# LCD.net
KiCad netlist of a schematic drawn in Altium Designer
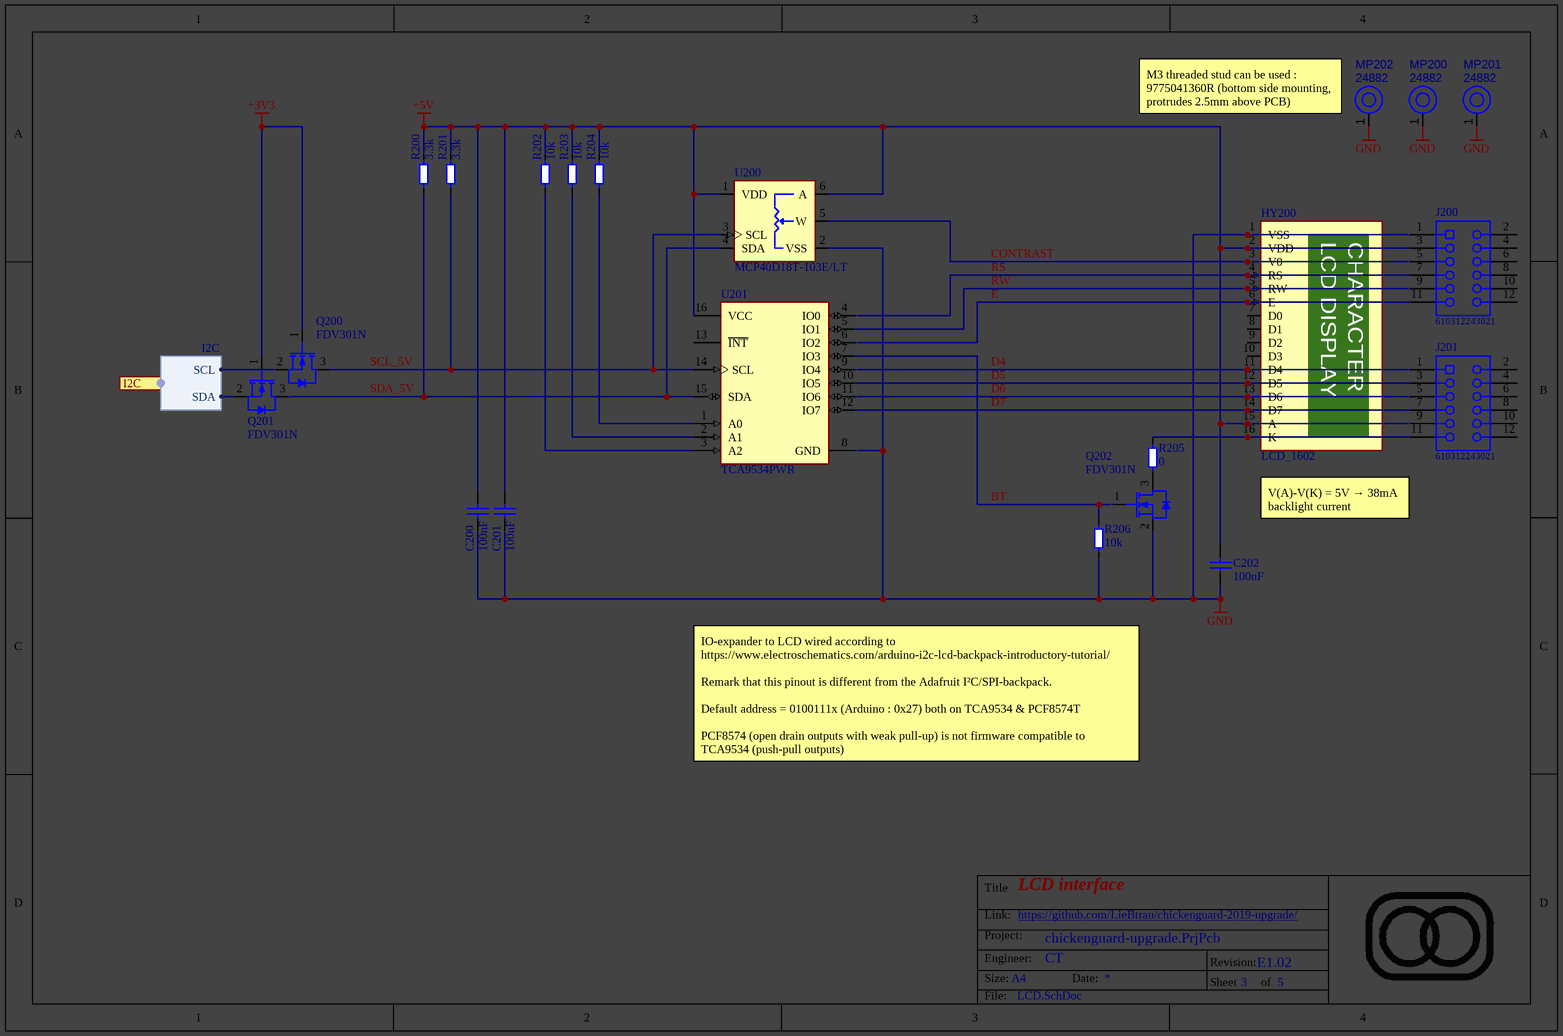
[diagram p0: LCD.SchDoc]

(export (version "E")
  (design (tool "Eeschema 10.0.6"))
  (components
    (comp (ref "C200")
      (value "100nF")
      (footprint "0603-C-L")
      (description "WCAP-CSGP Multilayer Ceramic Chip Capacitor, General Purpose, size 0603, X7R, 100nF, 25VDC")
      (fields (field (name "TOLERANCE") "10%") (field (name "Comment") "Capacitor 100nF +/-10% 25V X7R 0603"))
      (libsource (lib "7c7 Engineering") (part "CAP-NP-2"))
    )
    (comp (ref "C201")
      (value "100nF")
      (footprint "0603-C-L")
      (description "WCAP-CSGP Multilayer Ceramic Chip Capacitor, General Purpose, size 0603, X7R, 100nF, 25VDC")
      (fields (field (name "TOLERANCE") "10%") (field (name "Comment") "Capacitor 100nF +/-10% 25V X7R 0603"))
      (libsource (lib "7c7 Engineering") (part "CAP-NP-2"))
    )
    (comp (ref "C202")
      (value "100nF")
      (footprint "0603-C-L")
      (description "WCAP-CSGP Multilayer Ceramic Chip Capacitor, General Purpose, size 0603, X7R, 100nF, 25VDC")
      (fields (field (name "TOLERANCE") "10%") (field (name "Comment") "Capacitor 100nF +/-10% 25V X7R 0603"))
      (libsource (lib "7c7 Engineering") (part "CAP-NP-2"))
    )
    (comp (ref "HY200")
      (value "LCD_1602")
      (footprint "LCD_1602-BottomEntry")
      (description "2x16 character LCD display")
      (libsource (lib "7c7 Engineering") (part "CHAR_LCD_PARALLEL"))
    )
    (comp (ref "J200")
      (value "610312243021")
      (footprint "610312243021")
      (description "WR-PHD Socket Header, SMT, pitch 2.54mm, Dual Row, Vertical, 12p")
      (fields (field (name "MANUFACTURER") "Wurth Elektronik"))
      (libsource (lib "7c7 Engineering") (part "Symbol"))
    )
    (comp (ref "J201")
      (value "610312243021")
      (footprint "610312243021")
      (description "WR-PHD Socket Header, SMT, pitch 2.54mm, Dual Row, Vertical, 12p")
      (fields (field (name "MANUFACTURER") "Wurth Elektronik"))
      (libsource (lib "7c7 Engineering") (part "Symbol"))
    )
    (comp (ref "MP200")
      (value "24882")
      (footprint "24882-Footprint-1")
      (description "Steel SMT Standoff, M3 - 3mm L")
      (libsource (lib "7c7 Engineering") (part "MECH_BOM"))
    )
    (comp (ref "MP201")
      (value "24882")
      (footprint "24882-Footprint-1")
      (description "Steel SMT Standoff, M3 - 3mm L")
      (libsource (lib "7c7 Engineering") (part "MECH_BOM"))
    )
    (comp (ref "MP202")
      (value "24882")
      (footprint "24882-Footprint-1")
      (description "Steel SMT Standoff, M3 - 3mm L")
      (libsource (lib "7c7 Engineering") (part "MECH_BOM"))
    )
    (comp (ref "Q200")
      (value "FDV301N")
      (footprint "SOT-23-3-N")
      (description "Transistor MOSFET N-Ch. 25V 220mA 0, 35W 4Ohm SOT23")
      (fields (field (name "JLCPCB PART #") "C15310"))
      (libsource (lib "7c7 Engineering") (part "NEMOS-GSD-3"))
    )
    (comp (ref "Q201")
      (value "FDV301N")
      (footprint "SOT-23-3-N")
      (description "Transistor MOSFET N-Ch. 25V 220mA 0, 35W 4Ohm SOT23")
      (fields (field (name "JLCPCB PART #") "C15310"))
      (libsource (lib "7c7 Engineering") (part "NEMOS-GSD-3"))
    )
    (comp (ref "Q202")
      (value "FDV301N")
      (footprint "SOT-23-3-N")
      (description "Transistor MOSFET N-Ch. 25V 220mA 0, 35W 4Ohm SOT23")
      (fields (field (name "JLCPCB PART #") "C15310"))
      (libsource (lib "7c7 Engineering") (part "NEMOS-GSD-3"))
    )
    (comp (ref "R200")
      (value "3.3k")
      (footprint "0603-R-N")
      (description "Chip Resistor, Thick Film, General Purpose, 0603, 100mW, 50V, 3.3 kOhm, +/-1%")
      (fields (field (name "TOLERANCE") "1%") (field (name "JLCPCB PART #") "C22978"))
      (libsource (lib "7c7 Engineering") (part "RES"))
    )
    (comp (ref "R201")
      (value "3.3k")
      (footprint "0603-R-N")
      (description "Chip Resistor, Thick Film, General Purpose, 0603, 100mW, 50V, 3.3 kOhm, +/-1%")
      (fields (field (name "TOLERANCE") "1%") (field (name "JLCPCB PART #") "C22978"))
      (libsource (lib "7c7 Engineering") (part "RES"))
    )
    (comp (ref "R202")
      (value "10k")
      (footprint "0603-R-N")
      (description "Chip Resistor, Thick Film, General Purpose, 0603, 100mW, 50V, 10 kOhm, +/-1%")
      (fields (field (name "TOLERANCE") "1%") (field (name "JLCPCB PART #") "C25804"))
      (libsource (lib "7c7 Engineering") (part "RES"))
    )
    (comp (ref "R203")
      (value "10k")
      (footprint "0603-R-N")
      (description "Chip Resistor, Thick Film, General Purpose, 0603, 100mW, 50V, 10 kOhm, +/-1%")
      (fields (field (name "TOLERANCE") "1%") (field (name "JLCPCB PART #") "C25804"))
      (libsource (lib "7c7 Engineering") (part "RES"))
    )
    (comp (ref "R204")
      (value "10k")
      (footprint "0603-R-N")
      (description "Chip Resistor, Thick Film, General Purpose, 0603, 100mW, 50V, 10 kOhm, +/-1%")
      (fields (field (name "TOLERANCE") "1%") (field (name "JLCPCB PART #") "C25804"))
      (libsource (lib "7c7 Engineering") (part "RES"))
    )
    (comp (ref "R205")
      (value "0")
      (footprint "0603-R-N")
      (description "Chip Jumper, Thick Film, Jumper, 0603, 100mW, 1A, 0 Ohm, <50 mOhm")
      (fields (field (name "TOLERANCE") "50 mOhm") (field (name "JLCPCB PART #") "C21189"))
      (libsource (lib "7c7 Engineering") (part "RES"))
    )
    (comp (ref "R206")
      (value "10k")
      (footprint "0603-R-N")
      (description "Chip Resistor, Thick Film, General Purpose, 0603, 100mW, 50V, 10 kOhm, +/-1%")
      (fields (field (name "TOLERANCE") "1%") (field (name "JLCPCB PART #") "C25804"))
      (libsource (lib "7c7 Engineering") (part "RES"))
    )
    (comp (ref "U200")
      (value "MCP40D18T-103E/LT")
      (footprint "SOT363-N")
      (description "Digital Potentiometer 10kOhm 128POS Volatile Linear Automotive 6-Pin SC-70 T/R")
      (fields (field (name "TOLERANCE") "20%"))
      (libsource (lib "7c7 Engineering") (part "IN-DPOT-MCP4018-6"))
    )
    (comp (ref "U201")
      (value "TCA9534PWR")
      (footprint "TSSOP16-0.65-4.4-L")
      (description "8-bit I/O expander, I2C/SMBus, 400kHz, 1.65 to 5.5V, TSSOP-16")
      (libsource (lib "7c7 Engineering") (part "04628dd91dbb09866b58f3fb2ae999f"))
    )
  )
  (nets
    (net (code "2") (name "+3V3") (class "Default")
      (node (ref "Q200") (pin "1") (pinfunction "G_1") (pintype "passive"))
      (node (ref "Q201") (pin "1") (pinfunction "G_1") (pintype "passive"))
    )
    (net (code "3") (name "+5V") (class "Default")
      (node (ref "C200") (pin "2") (pinfunction "2_2") (pintype "passive"))
      (node (ref "C201") (pin "2") (pinfunction "2_2") (pintype "passive"))
      (node (ref "C202") (pin "2") (pinfunction "2_2") (pintype "passive"))
      (node (ref "HY200") (pin "15") (pinfunction "A_15") (pintype "power_in"))
      (node (ref "HY200") (pin "2") (pinfunction "VDD_2") (pintype "power_in"))
      (node (ref "J200") (pin "3") (pinfunction "3_3") (pintype "passive"))
      (node (ref "J201") (pin "9") (pinfunction "9_9") (pintype "passive"))
      (node (ref "R200") (pin "2") (pinfunction "2_2") (pintype "passive"))
      (node (ref "R201") (pin "2") (pinfunction "2_2") (pintype "passive"))
      (node (ref "R202") (pin "2") (pinfunction "2_2") (pintype "passive"))
      (node (ref "R203") (pin "2") (pinfunction "2_2") (pintype "passive"))
      (node (ref "R204") (pin "2") (pinfunction "2_2") (pintype "passive"))
      (node (ref "U200") (pin "1") (pinfunction "VDD_1") (pintype "power_in"))
      (node (ref "U200") (pin "6") (pinfunction "A_6") (pintype "passive"))
      (node (ref "U201") (pin "16") (pinfunction "VCC_16") (pintype "power_in"))
    )
    (net (code "4") (name "/BT") (class "Default")
      (node (ref "Q202") (pin "1") (pinfunction "G_1") (pintype "passive"))
      (node (ref "R206") (pin "2") (pinfunction "2_2") (pintype "passive"))
      (node (ref "U201") (pin "7") (pinfunction "IO3_7") (pintype "bidirectional"))
    )
    (net (code "5") (name "/CONTRAST") (class "Default")
      (node (ref "HY200") (pin "3") (pinfunction "V0_3") (pintype "power_in"))
      (node (ref "J200") (pin "5") (pinfunction "5_5") (pintype "passive"))
      (node (ref "U200") (pin "5") (pinfunction "W_5") (pintype "passive"))
    )
    (net (code "6") (name "/D4") (class "Default")
      (node (ref "HY200") (pin "11") (pinfunction "D4_11") (pintype "bidirectional"))
      (node (ref "J201") (pin "1") (pinfunction "1_1") (pintype "passive"))
      (node (ref "U201") (pin "9") (pinfunction "IO4_9") (pintype "bidirectional"))
    )
    (net (code "7") (name "/D5") (class "Default")
      (node (ref "HY200") (pin "12") (pinfunction "D5_12") (pintype "bidirectional"))
      (node (ref "J201") (pin "3") (pinfunction "3_3") (pintype "passive"))
      (node (ref "U201") (pin "10") (pinfunction "IO5_10") (pintype "bidirectional"))
    )
    (net (code "8") (name "/D6") (class "Default")
      (node (ref "HY200") (pin "13") (pinfunction "D6_13") (pintype "bidirectional"))
      (node (ref "J201") (pin "5") (pinfunction "5_5") (pintype "passive"))
      (node (ref "U201") (pin "11") (pinfunction "IO6_11") (pintype "bidirectional"))
    )
    (net (code "9") (name "/D7") (class "Default")
      (node (ref "HY200") (pin "14") (pinfunction "D7_14") (pintype "bidirectional"))
      (node (ref "J201") (pin "7") (pinfunction "7_7") (pintype "passive"))
      (node (ref "U201") (pin "12") (pinfunction "IO7_12") (pintype "bidirectional"))
    )
    (net (code "10") (name "/E") (class "Default")
      (node (ref "HY200") (pin "6") (pinfunction "E_6") (pintype "input"))
      (node (ref "J200") (pin "11") (pinfunction "11_11") (pintype "passive"))
      (node (ref "U201") (pin "6") (pinfunction "IO2_6") (pintype "bidirectional"))
    )
    (net (code "11") (name "/RS") (class "Default")
      (node (ref "HY200") (pin "4") (pinfunction "RS_4") (pintype "input"))
      (node (ref "J200") (pin "7") (pinfunction "7_7") (pintype "passive"))
      (node (ref "U201") (pin "4") (pinfunction "IO0_4") (pintype "bidirectional"))
    )
    (net (code "12") (name "/RW") (class "Default")
      (node (ref "HY200") (pin "5") (pinfunction "RW_5") (pintype "input"))
      (node (ref "J200") (pin "9") (pinfunction "9_9") (pintype "passive"))
      (node (ref "U201") (pin "5") (pinfunction "IO1_5") (pintype "bidirectional"))
    )
    (net (code "13") (name "/SCL") (class "Default")
      (node (ref "Q200") (pin "2") (pinfunction "S_2") (pintype "passive"))
    )
    (net (code "14") (name "/SCL_5V") (class "Default")
      (node (ref "Q200") (pin "3") (pinfunction "D_3") (pintype "passive"))
      (node (ref "R201") (pin "1") (pinfunction "1_1") (pintype "passive"))
      (node (ref "U200") (pin "3") (pinfunction "SCL_3") (pintype "input"))
      (node (ref "U201") (pin "14") (pinfunction "SCL_14") (pintype "input"))
    )
    (net (code "15") (name "/SDA") (class "Default")
      (node (ref "Q201") (pin "2") (pinfunction "S_2") (pintype "passive"))
    )
    (net (code "16") (name "/SDA_5V") (class "Default")
      (node (ref "Q201") (pin "3") (pinfunction "D_3") (pintype "passive"))
      (node (ref "R200") (pin "1") (pinfunction "1_1") (pintype "passive"))
      (node (ref "U200") (pin "4") (pinfunction "SDA_4") (pintype "bidirectional"))
      (node (ref "U201") (pin "15") (pinfunction "SDA_15") (pintype "bidirectional"))
    )
    (net (code "18") (name "GND") (class "Default")
      (node (ref "C200") (pin "1") (pinfunction "1_1") (pintype "passive"))
      (node (ref "C201") (pin "1") (pinfunction "1_1") (pintype "passive"))
      (node (ref "C202") (pin "1") (pinfunction "1_1") (pintype "passive"))
      (node (ref "HY200") (pin "1") (pinfunction "VSS_1") (pintype "power_in"))
      (node (ref "J200") (pin "1") (pinfunction "1_1") (pintype "passive"))
      (node (ref "MP200") (pin "1") (pinfunction "H1_1") (pintype "passive"))
      (node (ref "MP201") (pin "1") (pinfunction "H1_1") (pintype "passive"))
      (node (ref "MP202") (pin "1") (pinfunction "H1_1") (pintype "passive"))
      (node (ref "Q202") (pin "2") (pinfunction "S_2") (pintype "passive"))
      (node (ref "R206") (pin "1") (pinfunction "1_1") (pintype "passive"))
      (node (ref "U200") (pin "2") (pinfunction "VSS_2") (pintype "power_in"))
      (node (ref "U201") (pin "8") (pinfunction "GND_8") (pintype "power_in"))
    )
    (net (code "19") (name "Net-(HY200-K)") (class "Default")
      (node (ref "HY200") (pin "16") (pinfunction "K_16") (pintype "power_in"))
      (node (ref "J201") (pin "11") (pinfunction "11_11") (pintype "passive"))
      (node (ref "R205") (pin "2") (pinfunction "2_2") (pintype "passive"))
    )
    (net (code "20") (name "Net-(Q202-D)") (class "Default")
      (node (ref "Q202") (pin "3") (pinfunction "D_3") (pintype "passive"))
      (node (ref "R205") (pin "1") (pinfunction "1_1") (pintype "passive"))
    )
    (net (code "21") (name "Net-(U201-A0)") (class "Default")
      (node (ref "R204") (pin "1") (pinfunction "1_1") (pintype "passive"))
      (node (ref "U201") (pin "1") (pinfunction "A0_1") (pintype "input"))
    )
    (net (code "22") (name "Net-(U201-A1)") (class "Default")
      (node (ref "R203") (pin "1") (pinfunction "1_1") (pintype "passive"))
      (node (ref "U201") (pin "2") (pinfunction "A1_2") (pintype "input"))
    )
    (net (code "23") (name "Net-(U201-A2)") (class "Default")
      (node (ref "R202") (pin "1") (pinfunction "1_1") (pintype "passive"))
      (node (ref "U201") (pin "3") (pinfunction "A2_3") (pintype "input"))
    )
    (net (code "24") (name "unconnected-(HY200-D0-Pad7)") (class "Default")
      (node (ref "HY200") (pin "7") (pinfunction "D0_7") (pintype "bidirectional"))
    )
    (net (code "25") (name "unconnected-(HY200-D1-Pad8)") (class "Default")
      (node (ref "HY200") (pin "8") (pinfunction "D1_8") (pintype "bidirectional"))
    )
    (net (code "26") (name "unconnected-(HY200-D2-Pad9)") (class "Default")
      (node (ref "HY200") (pin "9") (pinfunction "D2_9") (pintype "bidirectional"))
    )
    (net (code "27") (name "unconnected-(HY200-D3-Pad10)") (class "Default")
      (node (ref "HY200") (pin "10") (pinfunction "D3_10") (pintype "bidirectional"))
    )
    (net (code "28") (name "unconnected-(J200-Pad2)") (class "Default")
      (node (ref "J200") (pin "2") (pinfunction "2_2") (pintype "passive"))
    )
    (net (code "29") (name "unconnected-(J200-Pad4)") (class "Default")
      (node (ref "J200") (pin "4") (pinfunction "4_4") (pintype "passive"))
    )
    (net (code "30") (name "unconnected-(J200-Pad6)") (class "Default")
      (node (ref "J200") (pin "6") (pinfunction "6_6") (pintype "passive"))
    )
    (net (code "31") (name "unconnected-(J200-Pad8)") (class "Default")
      (node (ref "J200") (pin "8") (pinfunction "8_8") (pintype "passive"))
    )
    (net (code "32") (name "unconnected-(J200-Pad10)") (class "Default")
      (node (ref "J200") (pin "10") (pinfunction "10_10") (pintype "passive"))
    )
    (net (code "33") (name "unconnected-(J200-Pad12)") (class "Default")
      (node (ref "J200") (pin "12") (pinfunction "12_12") (pintype "passive"))
    )
    (net (code "34") (name "unconnected-(J201-Pad2)") (class "Default")
      (node (ref "J201") (pin "2") (pinfunction "2_2") (pintype "passive"))
    )
    (net (code "35") (name "unconnected-(J201-Pad4)") (class "Default")
      (node (ref "J201") (pin "4") (pinfunction "4_4") (pintype "passive"))
    )
    (net (code "36") (name "unconnected-(J201-Pad6)") (class "Default")
      (node (ref "J201") (pin "6") (pinfunction "6_6") (pintype "passive"))
    )
    (net (code "37") (name "unconnected-(J201-Pad8)") (class "Default")
      (node (ref "J201") (pin "8") (pinfunction "8_8") (pintype "passive"))
    )
    (net (code "38") (name "unconnected-(J201-Pad10)") (class "Default")
      (node (ref "J201") (pin "10") (pinfunction "10_10") (pintype "passive"))
    )
    (net (code "39") (name "unconnected-(J201-Pad12)") (class "Default")
      (node (ref "J201") (pin "12") (pinfunction "12_12") (pintype "passive"))
    )
    (net (code "40") (name "unconnected-(U201-~{INT}-Pad13)") (class "Default")
      (node (ref "U201") (pin "13") (pinfunction "~{INT}_13") (pintype "open_collector"))
    )
  )
)
